# olm-sqw2.net
KiCad netlist of a schematic drawn in EAGLE
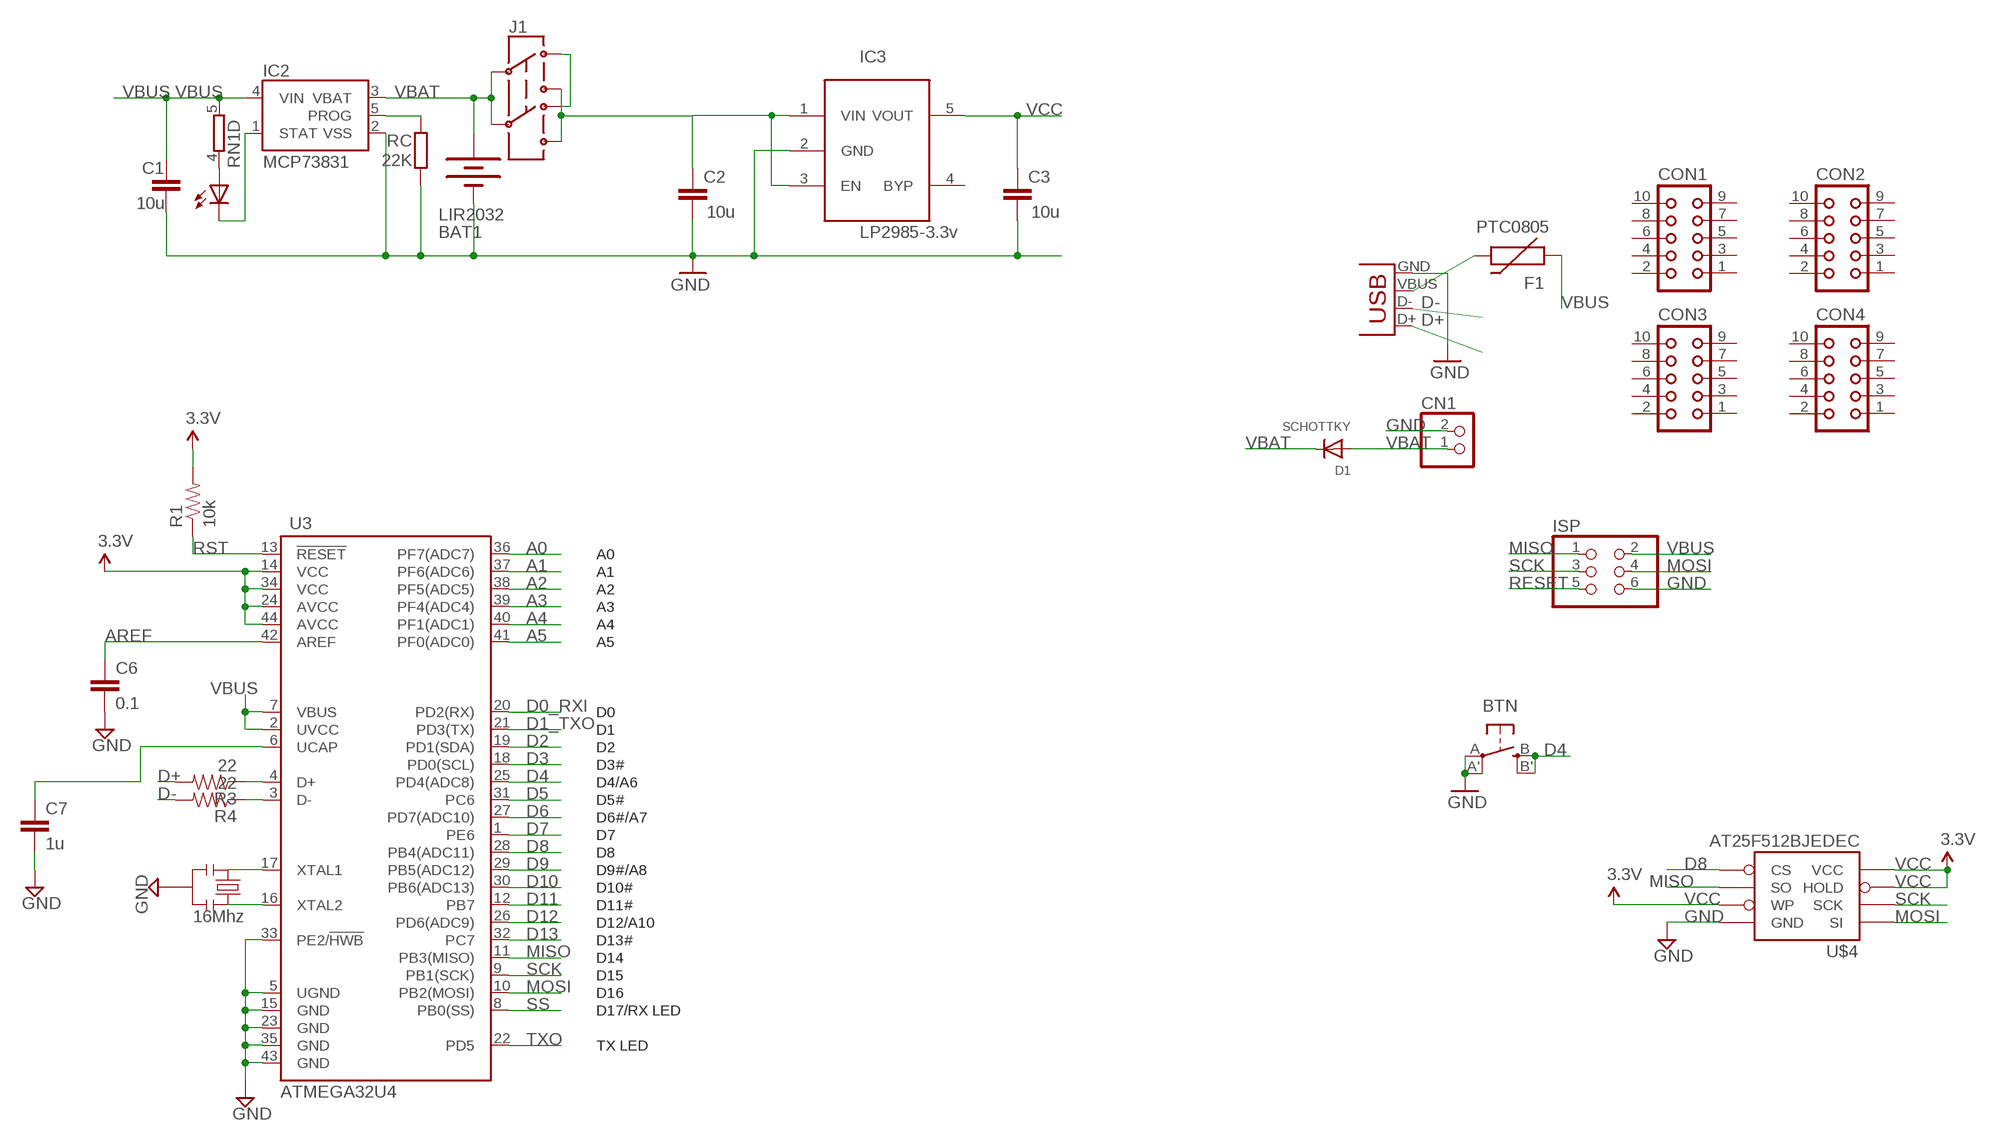
[diagram p0: schematic, sheet 1]

(export (version "E")
  (design (tool "Eeschema 10.0.6"))
  (components
    (comp (ref "BAT1")
      (value "LIR2032")
      (footprint "eagle-import:BATTCOM_20MM_PTH_SMT")
      (libsource (lib "eagle-import") (part "BATTERYBATTCOM_20MM_PTH_SMT"))
    )
    (comp (ref "BTN")
      (value "EVQQ2")
      (footprint "eagle-import:EVQ-Q2")
      (libsource (lib "eagle-import") (part "EVQQ2"))
    )
    (comp (ref "C1")
      (value "10u")
      (footprint "eagle-import:C0805")
      (libsource (lib "eagle-import") (part "C-EUC0805"))
    )
    (comp (ref "C2")
      (value "10u")
      (footprint "eagle-import:C0805")
      (libsource (lib "eagle-import") (part "C-EUC0805"))
    )
    (comp (ref "C3")
      (value "10u")
      (footprint "eagle-import:C0805")
      (libsource (lib "eagle-import") (part "C-EUC0805"))
    )
    (comp (ref "C6")
      (value "0.1")
      (footprint "eagle-import:0603-CAP")
      (libsource (lib "eagle-import") (part "CAP0603-CAP"))
    )
    (comp (ref "C7")
      (value "1u")
      (footprint "eagle-import:0603-CAP")
      (libsource (lib "eagle-import") (part "CAP0603-CAP"))
    )
    (comp (ref "CHG")
      (value "0805")
      (footprint "eagle-import:CHIPLED_0805")
      (libsource (lib "eagle-import") (part "LEDCHIPLED_0805"))
    )
    (comp (ref "CN1")
      (value "JST_2PIN-SMT-RA")
      (footprint "eagle-import:JST-PH-2-SMT-RA")
      (libsource (lib "eagle-import") (part "JST_2PIN-SMT-RA"))
    )
    (comp (ref "CON1")
      (value "CON10")
      (footprint "eagle-import:CON10")
      (libsource (lib "eagle-import") (part "CON10"))
    )
    (comp (ref "CON2")
      (value "CON10")
      (footprint "eagle-import:CON10")
      (libsource (lib "eagle-import") (part "CON10"))
    )
    (comp (ref "CON3")
      (value "CON10")
      (footprint "eagle-import:CON10")
      (libsource (lib "eagle-import") (part "CON10"))
    )
    (comp (ref "CON4")
      (value "CON10")
      (footprint "eagle-import:CON10")
      (libsource (lib "eagle-import") (part "CON10"))
    )
    (comp (ref "D1")
      (value "SCHOTTKY")
      (footprint "eagle-import:SOD-123")
      (libsource (lib "eagle-import") (part "DIODESOD-123"))
    )
    (comp (ref "F1")
      (value "PTC0805")
      (footprint "eagle-import:0805-PTC")
      (libsource (lib "eagle-import") (part "PTC0805"))
    )
    (comp (ref "IC2")
      (value "MCP73831")
      (footprint "eagle-import:SOT23-5")
      (libsource (lib "eagle-import") (part "MCP73831"))
    )
    (comp (ref "IC3")
      (value "LP2985-3.3v")
      (footprint "eagle-import:SOT23-5L")
      (libsource (lib "eagle-import") (part "LP298XS"))
    )
    (comp (ref "ISP")
      (value "PINHD-2X3")
      (footprint "eagle-import:2X03")
      (libsource (lib "eagle-import") (part "PINHD-2X3"))
    )
    (comp (ref "J1")
      (value "AYZ0202")
      (footprint "eagle-import:AYZ0202")
      (libsource (lib "eagle-import") (part "AYZ0202"))
    )
    (comp (ref "R1")
      (value "10k")
      (footprint "eagle-import:0603-RES")
      (libsource (lib "eagle-import") (part "RESISTOR0603-RES"))
    )
    (comp (ref "R3")
      (value "22")
      (footprint "eagle-import:0603-RES")
      (libsource (lib "eagle-import") (part "RESISTOR0603-RES"))
    )
    (comp (ref "R4")
      (value "22")
      (footprint "eagle-import:0603-RES")
      (libsource (lib "eagle-import") (part "RESISTOR0603-RES"))
    )
    (comp (ref "RC")
      (value "22K")
      (footprint "eagle-import:R0805")
      (libsource (lib "eagle-import") (part "R-EU_R0805"))
    )
    (comp (ref "RN1")
      (value "4R-NEXB38V")
      (footprint "eagle-import:EXB38V")
      (libsource (lib "eagle-import") (part "4R-NEXB38V"))
    )
    (comp (ref "U$4")
      (value "AT25F512BJEDEC")
      (footprint "eagle-import:SO08")
      (libsource (lib "eagle-import") (part "AT25F512BJEDEC"))
    )
    (comp (ref "U3")
      (value "ATMEGA32U4")
      (footprint "eagle-import:QFN-44-NOPAD")
      (libsource (lib "eagle-import") (part "ATMEGA32U4QFN2"))
    )
    (comp (ref "X1")
      (value "USBSMD")
      (footprint "eagle-import:USB-MINIB")
      (libsource (lib "eagle-import") (part "USBSMD"))
    )
    (comp (ref "X2")
      (value "16Mhz")
      (footprint "eagle-import:RESONATOR-SMD")
      (libsource (lib "eagle-import") (part "RESONATORSMD"))
    )
  )
  (nets
    (net (code "1") (name "/A0") (class "Default")
      (node (ref "U3") (pin "36") (pinfunction "PF7(ADC7)_36") (pintype "bidirectional"))
    )
    (net (code "2") (name "/A1") (class "Default")
      (node (ref "U3") (pin "37") (pinfunction "PF6(ADC6)_37") (pintype "bidirectional"))
    )
    (net (code "3") (name "/A2") (class "Default")
      (node (ref "U3") (pin "38") (pinfunction "PF5(ADC5)_38") (pintype "bidirectional"))
    )
    (net (code "4") (name "/A3") (class "Default")
      (node (ref "U3") (pin "39") (pinfunction "PF4(ADC4)_39") (pintype "bidirectional"))
    )
    (net (code "5") (name "/A4") (class "Default")
      (node (ref "U3") (pin "40") (pinfunction "PF1(ADC1)_40") (pintype "bidirectional"))
    )
    (net (code "6") (name "/A5") (class "Default")
      (node (ref "U3") (pin "41") (pinfunction "PF0(ADC0)_41") (pintype "bidirectional"))
    )
    (net (code "7") (name "/AREF") (class "Default")
      (node (ref "C6") (pin "1") (pinfunction "1_1") (pintype "passive"))
      (node (ref "U3") (pin "42") (pinfunction "AREF_42") (pintype "bidirectional"))
    )
    (net (code "8") (name "/D+") (class "Default")
      (node (ref "R3") (pin "2") (pinfunction "2_2") (pintype "passive"))
      (node (ref "X1") (pin "D+") (pinfunction "D+_D+") (pintype "bidirectional"))
    )
    (net (code "9") (name "/D-") (class "Default")
      (node (ref "R4") (pin "2") (pinfunction "2_2") (pintype "passive"))
      (node (ref "X1") (pin "D-") (pinfunction "D-_D-") (pintype "bidirectional"))
    )
    (net (code "10") (name "/D0_RXI") (class "Default")
      (node (ref "U3") (pin "20") (pinfunction "PD2(RX)_20") (pintype "bidirectional"))
    )
    (net (code "11") (name "/D1_TXO") (class "Default")
      (node (ref "U3") (pin "21") (pinfunction "PD3(TX)_21") (pintype "bidirectional"))
    )
    (net (code "12") (name "/D2") (class "Default")
      (node (ref "U3") (pin "19") (pinfunction "PD1(SDA)_19") (pintype "bidirectional"))
    )
    (net (code "13") (name "/D3") (class "Default")
      (node (ref "U3") (pin "18") (pinfunction "PD0(SCL)_18") (pintype "bidirectional"))
    )
    (net (code "14") (name "/D4") (class "Default")
      (node (ref "BTN") (pin "B") (pinfunction "S_B") (pintype "passive"))
      (node (ref "BTN") (pin "B'") (pinfunction "S1_B'") (pintype "passive"))
      (node (ref "U3") (pin "25") (pinfunction "PD4(ADC8)_25") (pintype "bidirectional"))
    )
    (net (code "15") (name "/D5") (class "Default")
      (node (ref "U3") (pin "31") (pinfunction "PC6_31") (pintype "bidirectional"))
    )
    (net (code "16") (name "/D6") (class "Default")
      (node (ref "U3") (pin "27") (pinfunction "PD7(ADC10)_27") (pintype "bidirectional"))
    )
    (net (code "17") (name "/D7") (class "Default")
      (node (ref "U3") (pin "1") (pinfunction "PE6_1") (pintype "bidirectional"))
    )
    (net (code "18") (name "/D8") (class "Default")
      (node (ref "U$4") (pin "1_CS") (pinfunction "CS_1_CS") (pintype "bidirectional"))
      (node (ref "U3") (pin "28") (pinfunction "PB4(ADC11)_28") (pintype "bidirectional"))
    )
    (net (code "19") (name "/D9") (class "Default")
      (node (ref "U3") (pin "29") (pinfunction "PB5(ADC12)_29") (pintype "bidirectional"))
    )
    (net (code "20") (name "/D10") (class "Default")
      (node (ref "U3") (pin "30") (pinfunction "PB6(ADC13)_30") (pintype "bidirectional"))
    )
    (net (code "21") (name "/D11") (class "Default")
      (node (ref "U3") (pin "12") (pinfunction "PB7_12") (pintype "bidirectional"))
    )
    (net (code "22") (name "/D12") (class "Default")
      (node (ref "U3") (pin "26") (pinfunction "PD6(ADC9)_26") (pintype "bidirectional"))
    )
    (net (code "23") (name "/D13") (class "Default")
      (node (ref "U3") (pin "32") (pinfunction "PC7_32") (pintype "bidirectional"))
    )
    (net (code "24") (name "/MISO") (class "Default")
      (node (ref "ISP") (pin "1") (pinfunction "1_1") (pintype "passive"))
      (node (ref "U$4") (pin "2_SO") (pinfunction "SO_2_SO") (pintype "bidirectional"))
      (node (ref "U3") (pin "11") (pinfunction "PB3(MISO)_11") (pintype "bidirectional"))
    )
    (net (code "25") (name "/MOSI") (class "Default")
      (node (ref "ISP") (pin "4") (pinfunction "4_4") (pintype "passive"))
      (node (ref "U$4") (pin "5_SI") (pinfunction "SI_5_SI") (pintype "bidirectional"))
      (node (ref "U3") (pin "10") (pinfunction "PB2(MOSI)_10") (pintype "bidirectional"))
    )
    (net (code "26") (name "/RESET") (class "Default")
      (node (ref "ISP") (pin "5") (pinfunction "5_5") (pintype "passive"))
    )
    (net (code "27") (name "/RST") (class "Default")
      (node (ref "R1") (pin "1") (pinfunction "1_1") (pintype "passive"))
      (node (ref "U3") (pin "13") (pinfunction "~{RESET}_13") (pintype "bidirectional"))
    )
    (net (code "28") (name "/SCK") (class "Default")
      (node (ref "ISP") (pin "3") (pinfunction "3_3") (pintype "passive"))
      (node (ref "U$4") (pin "6_SCK") (pinfunction "SCK_6_SCK") (pintype "bidirectional"))
      (node (ref "U3") (pin "9") (pinfunction "PB1(SCK)_9") (pintype "bidirectional"))
    )
    (net (code "29") (name "/SS") (class "Default")
      (node (ref "U3") (pin "8") (pinfunction "PB0(SS)_8") (pintype "bidirectional"))
    )
    (net (code "30") (name "/TXO") (class "Default")
      (node (ref "U3") (pin "22") (pinfunction "PD5_22") (pintype "bidirectional"))
    )
    (net (code "31") (name "/VBAT") (class "Default")
      (node (ref "BAT1") (pin "P$2") (pinfunction "+_P$2") (pintype "power_in"))
      (node (ref "CN1") (pin "1") (pinfunction "2_1") (pintype "passive"))
      (node (ref "D1") (pin "A") (pinfunction "A_A") (pintype "passive"))
      (node (ref "D1") (pin "C") (pinfunction "C_C") (pintype "passive"))
      (node (ref "IC2") (pin "3") (pinfunction "VBAT_3") (pintype "power_in"))
      (node (ref "J1") (pin "2") (pinfunction "2_2") (pintype "bidirectional"))
      (node (ref "J1") (pin "5") (pinfunction "5_5") (pintype "bidirectional"))
    )
    (net (code "32") (name "/VBUS") (class "Default")
      (node (ref "C1") (pin "1") (pinfunction "1_1") (pintype "passive"))
      (node (ref "F1") (pin "1") (pinfunction "1_1") (pintype "bidirectional"))
      (node (ref "F1") (pin "2") (pinfunction "2_2") (pintype "bidirectional"))
      (node (ref "IC2") (pin "4") (pinfunction "VIN_4") (pintype "power_in"))
      (node (ref "ISP") (pin "2") (pinfunction "2_2") (pintype "passive"))
      (node (ref "RN1") (pin "5") (pinfunction "2_5") (pintype "passive"))
      (node (ref "U3") (pin "2") (pinfunction "UVCC_2") (pintype "bidirectional"))
      (node (ref "U3") (pin "7") (pinfunction "VBUS_7") (pintype "bidirectional"))
      (node (ref "X1") (pin "VBUS") (pinfunction "VBUS_VBUS") (pintype "bidirectional"))
    )
    (net (code "33") (name "3.3V") (class "Default")
      (node (ref "C3") (pin "1") (pinfunction "1_1") (pintype "passive"))
      (node (ref "IC3") (pin "5") (pinfunction "VOUT_5") (pintype "bidirectional"))
      (node (ref "R1") (pin "2") (pinfunction "2_2") (pintype "passive"))
      (node (ref "U$4") (pin "3_WP") (pinfunction "WP_3_WP") (pintype "bidirectional"))
      (node (ref "U$4") (pin "7_HOLD") (pinfunction "HOLD_7_HOLD") (pintype "bidirectional"))
      (node (ref "U$4") (pin "8_VCC") (pinfunction "VCC_8_VCC") (pintype "bidirectional"))
      (node (ref "U3") (pin "14") (pinfunction "VCC_14") (pintype "bidirectional"))
      (node (ref "U3") (pin "24") (pinfunction "AVCC_24") (pintype "bidirectional"))
      (node (ref "U3") (pin "34") (pinfunction "VCC_34") (pintype "bidirectional"))
      (node (ref "U3") (pin "44") (pinfunction "AVCC_44") (pintype "bidirectional"))
    )
    (net (code "34") (name "GND") (class "Default")
      (node (ref "BAT1") (pin "P$1") (pinfunction "-_P$1") (pintype "power_in"))
      (node (ref "BTN") (pin "A") (pinfunction "P_A") (pintype "passive"))
      (node (ref "BTN") (pin "A'") (pinfunction "P1_A'") (pintype "passive"))
      (node (ref "C1") (pin "2") (pinfunction "2_2") (pintype "passive"))
      (node (ref "C2") (pin "2") (pinfunction "2_2") (pintype "passive"))
      (node (ref "C3") (pin "2") (pinfunction "2_2") (pintype "passive"))
      (node (ref "C6") (pin "2") (pinfunction "2_2") (pintype "passive"))
      (node (ref "C7") (pin "2") (pinfunction "2_2") (pintype "passive"))
      (node (ref "CN1") (pin "2") (pinfunction "1_2") (pintype "passive"))
      (node (ref "IC2") (pin "2") (pinfunction "VSS_2") (pintype "power_in"))
      (node (ref "IC3") (pin "2") (pinfunction "GND_2") (pintype "bidirectional"))
      (node (ref "ISP") (pin "6") (pinfunction "6_6") (pintype "passive"))
      (node (ref "RC") (pin "1") (pinfunction "1_1") (pintype "passive"))
      (node (ref "U$4") (pin "4_GND") (pinfunction "GND_4_GND") (pintype "bidirectional"))
      (node (ref "U3") (pin "15") (pinfunction "GND_15") (pintype "bidirectional"))
      (node (ref "U3") (pin "23") (pinfunction "GND_23") (pintype "bidirectional"))
      (node (ref "U3") (pin "33") (pinfunction "PE2/~{HWB}_33") (pintype "bidirectional"))
      (node (ref "U3") (pin "35") (pinfunction "GND_35") (pintype "bidirectional"))
      (node (ref "U3") (pin "43") (pinfunction "GND_43") (pintype "bidirectional"))
      (node (ref "U3") (pin "5") (pinfunction "UGND_5") (pintype "bidirectional"))
      (node (ref "X1") (pin "GND") (pinfunction "GND_GND") (pintype "bidirectional"))
      (node (ref "X2") (pin "2") (pinfunction "2_2") (pintype "passive"))
    )
    (net (code "35") (name "Net-(IC2-PROG)") (class "Default")
      (node (ref "IC2") (pin "5") (pinfunction "PROG_5") (pintype "input"))
      (node (ref "RC") (pin "2") (pinfunction "2_2") (pintype "passive"))
    )
    (net (code "36") (name "Net-(IC2-STAT)") (class "Default")
      (node (ref "CHG") (pin "C") (pinfunction "C_C") (pintype "passive"))
      (node (ref "IC2") (pin "1") (pinfunction "STAT_1") (pintype "output"))
    )
    (net (code "37") (name "Net-(IC3-EN)") (class "Default")
      (node (ref "C2") (pin "1") (pinfunction "1_1") (pintype "passive"))
      (node (ref "IC3") (pin "1") (pinfunction "VIN_1") (pintype "bidirectional"))
      (node (ref "IC3") (pin "3") (pinfunction "EN_3") (pintype "bidirectional"))
      (node (ref "J1") (pin "1") (pinfunction "3_1") (pintype "bidirectional"))
      (node (ref "J1") (pin "4") (pinfunction "6_4") (pintype "bidirectional"))
    )
    (net (code "38") (name "Net-(J1-1)") (class "Default")
      (node (ref "J1") (pin "3") (pinfunction "1_3") (pintype "bidirectional"))
      (node (ref "J1") (pin "6") (pinfunction "4_6") (pintype "bidirectional"))
    )
    (net (code "39") (name "Net-(RN1D-1)") (class "Default")
      (node (ref "CHG") (pin "A") (pinfunction "A_A") (pintype "passive"))
      (node (ref "RN1") (pin "4") (pinfunction "1_4") (pintype "passive"))
    )
    (net (code "40") (name "Net-(U3-D+)") (class "Default")
      (node (ref "R3") (pin "1") (pinfunction "1_1") (pintype "passive"))
      (node (ref "U3") (pin "4") (pinfunction "D+_4") (pintype "bidirectional"))
    )
    (net (code "41") (name "Net-(U3-D-)") (class "Default")
      (node (ref "R4") (pin "1") (pinfunction "1_1") (pintype "passive"))
      (node (ref "U3") (pin "3") (pinfunction "D-_3") (pintype "bidirectional"))
    )
    (net (code "42") (name "Net-(U3-UCAP)") (class "Default")
      (node (ref "C7") (pin "1") (pinfunction "1_1") (pintype "passive"))
      (node (ref "U3") (pin "6") (pinfunction "UCAP_6") (pintype "bidirectional"))
    )
    (net (code "43") (name "Net-(U3-XTAL1)") (class "Default")
      (node (ref "U3") (pin "17") (pinfunction "XTAL1_17") (pintype "bidirectional"))
      (node (ref "X2") (pin "1") (pinfunction "1_1") (pintype "passive"))
    )
    (net (code "44") (name "Net-(U3-XTAL2)") (class "Default")
      (node (ref "U3") (pin "16") (pinfunction "XTAL2_16") (pintype "bidirectional"))
      (node (ref "X2") (pin "3") (pinfunction "3_3") (pintype "passive"))
    )
    (net (code "45") (name "unconnected-(CON1-Pad1)") (class "Default")
      (node (ref "CON1") (pin "1") (pinfunction "1_1") (pintype "passive"))
    )
    (net (code "46") (name "unconnected-(CON1-Pad2)") (class "Default")
      (node (ref "CON1") (pin "2") (pinfunction "2_2") (pintype "passive"))
    )
    (net (code "47") (name "unconnected-(CON1-Pad3)") (class "Default")
      (node (ref "CON1") (pin "3") (pinfunction "3_3") (pintype "passive"))
    )
    (net (code "48") (name "unconnected-(CON1-Pad4)") (class "Default")
      (node (ref "CON1") (pin "4") (pinfunction "4_4") (pintype "passive"))
    )
    (net (code "49") (name "unconnected-(CON1-Pad5)") (class "Default")
      (node (ref "CON1") (pin "5") (pinfunction "5_5") (pintype "passive"))
    )
    (net (code "50") (name "unconnected-(CON1-Pad6)") (class "Default")
      (node (ref "CON1") (pin "6") (pinfunction "6_6") (pintype "passive"))
    )
    (net (code "51") (name "unconnected-(CON1-Pad7)") (class "Default")
      (node (ref "CON1") (pin "7") (pinfunction "7_7") (pintype "passive"))
    )
    (net (code "52") (name "unconnected-(CON1-Pad8)") (class "Default")
      (node (ref "CON1") (pin "8") (pinfunction "8_8") (pintype "passive"))
    )
    (net (code "53") (name "unconnected-(CON1-Pad9)") (class "Default")
      (node (ref "CON1") (pin "9") (pinfunction "9_9") (pintype "passive"))
    )
    (net (code "54") (name "unconnected-(CON1-Pad10)") (class "Default")
      (node (ref "CON1") (pin "10") (pinfunction "10_10") (pintype "passive"))
    )
    (net (code "55") (name "unconnected-(CON2-Pad1)") (class "Default")
      (node (ref "CON2") (pin "1") (pinfunction "1_1") (pintype "passive"))
    )
    (net (code "56") (name "unconnected-(CON2-Pad2)") (class "Default")
      (node (ref "CON2") (pin "2") (pinfunction "2_2") (pintype "passive"))
    )
    (net (code "57") (name "unconnected-(CON2-Pad3)") (class "Default")
      (node (ref "CON2") (pin "3") (pinfunction "3_3") (pintype "passive"))
    )
    (net (code "58") (name "unconnected-(CON2-Pad4)") (class "Default")
      (node (ref "CON2") (pin "4") (pinfunction "4_4") (pintype "passive"))
    )
    (net (code "59") (name "unconnected-(CON2-Pad5)") (class "Default")
      (node (ref "CON2") (pin "5") (pinfunction "5_5") (pintype "passive"))
    )
    (net (code "60") (name "unconnected-(CON2-Pad6)") (class "Default")
      (node (ref "CON2") (pin "6") (pinfunction "6_6") (pintype "passive"))
    )
    (net (code "61") (name "unconnected-(CON2-Pad7)") (class "Default")
      (node (ref "CON2") (pin "7") (pinfunction "7_7") (pintype "passive"))
    )
    (net (code "62") (name "unconnected-(CON2-Pad8)") (class "Default")
      (node (ref "CON2") (pin "8") (pinfunction "8_8") (pintype "passive"))
    )
    (net (code "63") (name "unconnected-(CON2-Pad9)") (class "Default")
      (node (ref "CON2") (pin "9") (pinfunction "9_9") (pintype "passive"))
    )
    (net (code "64") (name "unconnected-(CON2-Pad10)") (class "Default")
      (node (ref "CON2") (pin "10") (pinfunction "10_10") (pintype "passive"))
    )
    (net (code "65") (name "unconnected-(CON3-Pad1)") (class "Default")
      (node (ref "CON3") (pin "1") (pinfunction "1_1") (pintype "passive"))
    )
    (net (code "66") (name "unconnected-(CON3-Pad2)") (class "Default")
      (node (ref "CON3") (pin "2") (pinfunction "2_2") (pintype "passive"))
    )
    (net (code "67") (name "unconnected-(CON3-Pad3)") (class "Default")
      (node (ref "CON3") (pin "3") (pinfunction "3_3") (pintype "passive"))
    )
    (net (code "68") (name "unconnected-(CON3-Pad4)") (class "Default")
      (node (ref "CON3") (pin "4") (pinfunction "4_4") (pintype "passive"))
    )
    (net (code "69") (name "unconnected-(CON3-Pad5)") (class "Default")
      (node (ref "CON3") (pin "5") (pinfunction "5_5") (pintype "passive"))
    )
    (net (code "70") (name "unconnected-(CON3-Pad6)") (class "Default")
      (node (ref "CON3") (pin "6") (pinfunction "6_6") (pintype "passive"))
    )
    (net (code "71") (name "unconnected-(CON3-Pad7)") (class "Default")
      (node (ref "CON3") (pin "7") (pinfunction "7_7") (pintype "passive"))
    )
    (net (code "72") (name "unconnected-(CON3-Pad8)") (class "Default")
      (node (ref "CON3") (pin "8") (pinfunction "8_8") (pintype "passive"))
    )
    (net (code "73") (name "unconnected-(CON3-Pad9)") (class "Default")
      (node (ref "CON3") (pin "9") (pinfunction "9_9") (pintype "passive"))
    )
    (net (code "74") (name "unconnected-(CON3-Pad10)") (class "Default")
      (node (ref "CON3") (pin "10") (pinfunction "10_10") (pintype "passive"))
    )
    (net (code "75") (name "unconnected-(CON4-Pad1)") (class "Default")
      (node (ref "CON4") (pin "1") (pinfunction "1_1") (pintype "passive"))
    )
    (net (code "76") (name "unconnected-(CON4-Pad2)") (class "Default")
      (node (ref "CON4") (pin "2") (pinfunction "2_2") (pintype "passive"))
    )
    (net (code "77") (name "unconnected-(CON4-Pad3)") (class "Default")
      (node (ref "CON4") (pin "3") (pinfunction "3_3") (pintype "passive"))
    )
    (net (code "78") (name "unconnected-(CON4-Pad4)") (class "Default")
      (node (ref "CON4") (pin "4") (pinfunction "4_4") (pintype "passive"))
    )
    (net (code "79") (name "unconnected-(CON4-Pad5)") (class "Default")
      (node (ref "CON4") (pin "5") (pinfunction "5_5") (pintype "passive"))
    )
    (net (code "80") (name "unconnected-(CON4-Pad6)") (class "Default")
      (node (ref "CON4") (pin "6") (pinfunction "6_6") (pintype "passive"))
    )
    (net (code "81") (name "unconnected-(CON4-Pad7)") (class "Default")
      (node (ref "CON4") (pin "7") (pinfunction "7_7") (pintype "passive"))
    )
    (net (code "82") (name "unconnected-(CON4-Pad8)") (class "Default")
      (node (ref "CON4") (pin "8") (pinfunction "8_8") (pintype "passive"))
    )
    (net (code "83") (name "unconnected-(CON4-Pad9)") (class "Default")
      (node (ref "CON4") (pin "9") (pinfunction "9_9") (pintype "passive"))
    )
    (net (code "84") (name "unconnected-(CON4-Pad10)") (class "Default")
      (node (ref "CON4") (pin "10") (pinfunction "10_10") (pintype "passive"))
    )
    (net (code "85") (name "unconnected-(IC3-BYP-Pad4)") (class "Default")
      (node (ref "IC3") (pin "4") (pinfunction "BYP_4") (pintype "bidirectional"))
    )
  )
)
